# EvaluationV1_0.net
KiCad netlist of a schematic drawn in Altium Designer
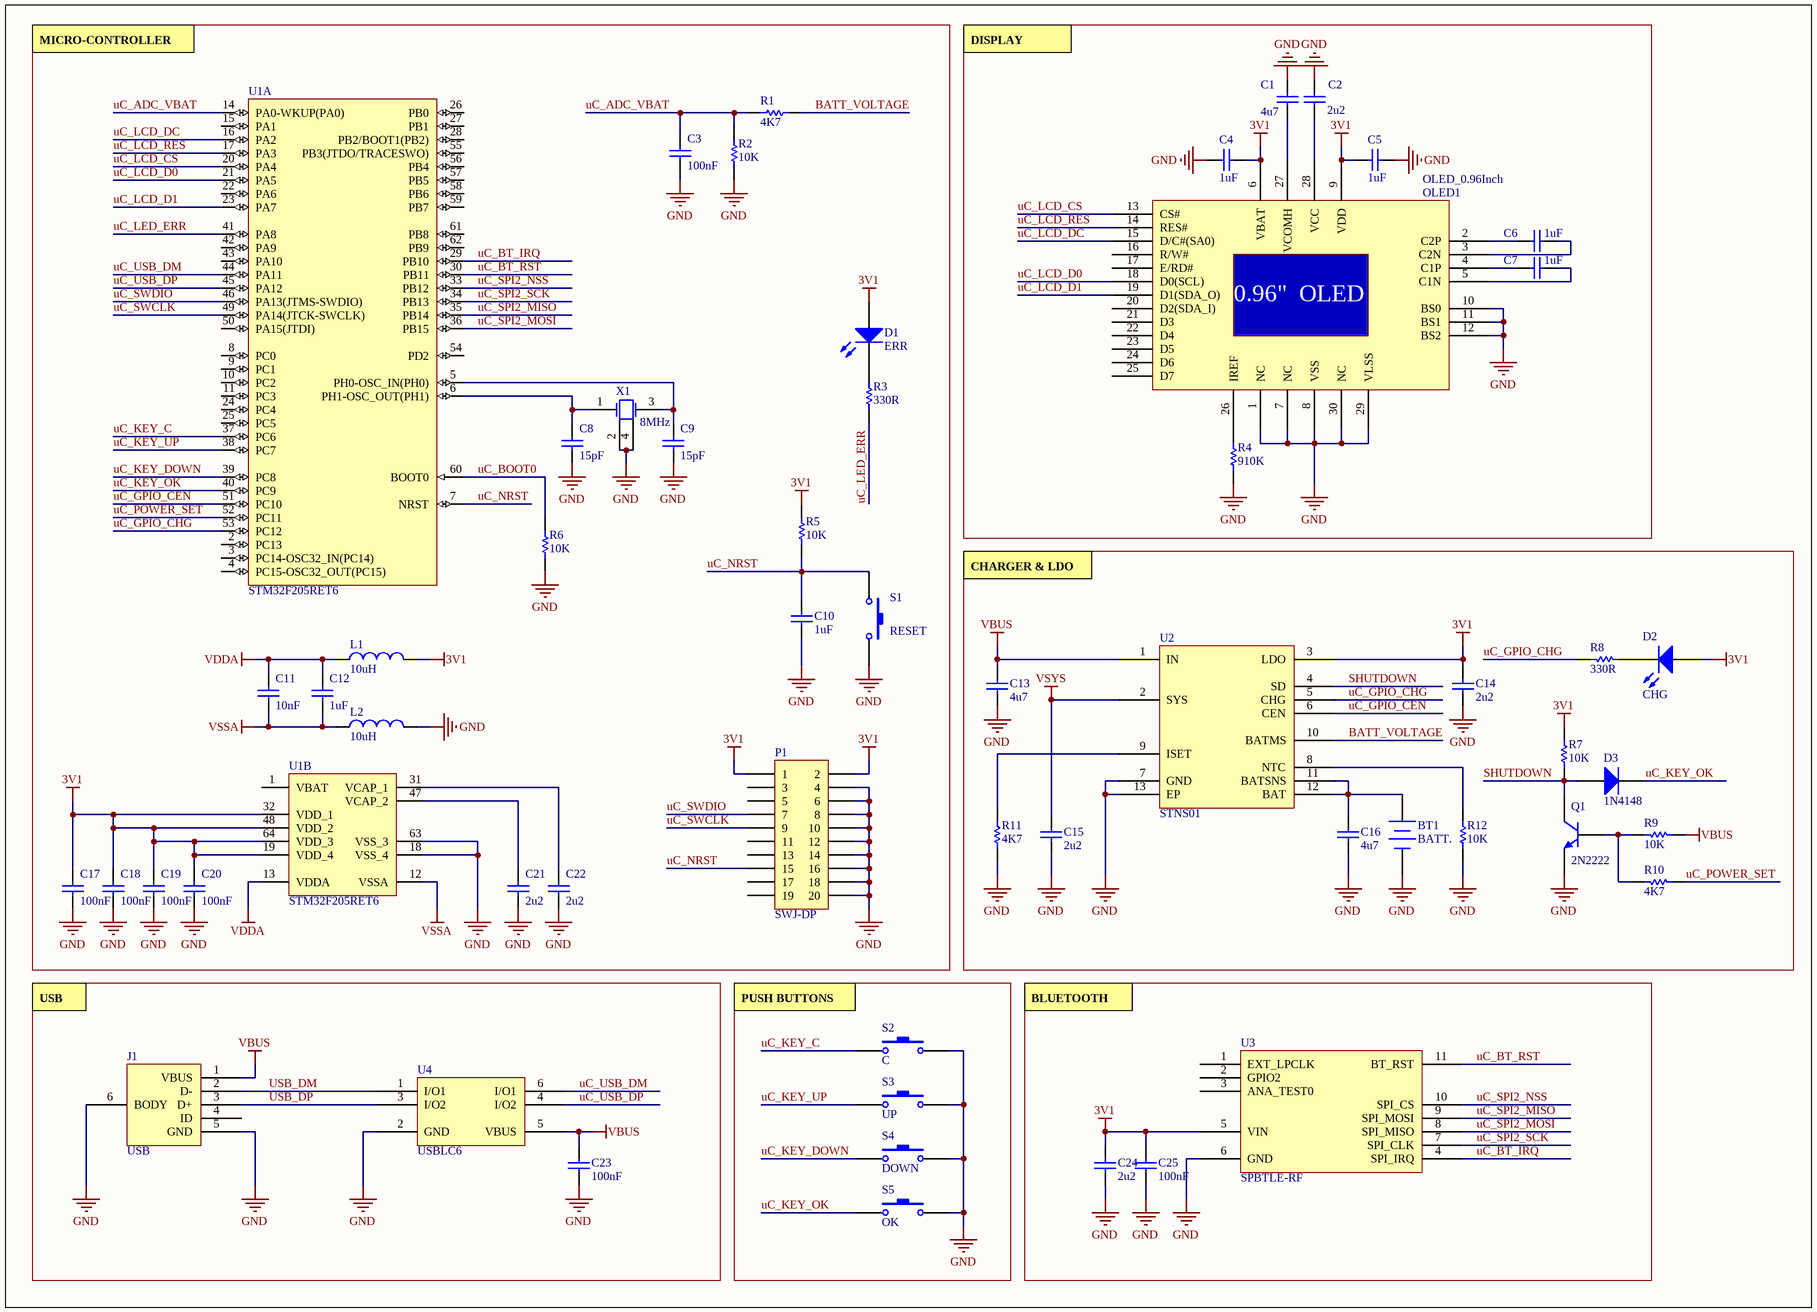
[diagram p0: EvaluationV1.0.SchDoc]

(export (version "E")
  (design (tool "Eeschema 10.0.6"))
  (components
    (comp (ref "BT1")
      (value "BATT.")
      (footprint "PH B2B")
      (description "Multicell Battery")
      (fields (field (name "PUBLISHER") "Altium Limited"))
      (libsource (lib "Miscellaneous Devices") (part "Battery"))
    )
    (comp (ref "C1")
      (value "4u7")
      (footprint "CAP 0805")
      (description "Multi Layer Capacitor")
      (libsource (lib "poyaLibrary") (part "CAP"))
    )
    (comp (ref "C2")
      (value "2u2")
      (footprint "CAP 0805")
      (description "Multi Layer Capacitor")
      (libsource (lib "poyaLibrary") (part "CAP"))
    )
    (comp (ref "C3")
      (value "100nF")
      (footprint "CAP 0805")
      (description "Multi Layer Capacitor")
      (libsource (lib "poyaLibrary") (part "CAP"))
    )
    (comp (ref "C4")
      (value "1uF")
      (footprint "CAP 0805")
      (description "Multi Layer Capacitor")
      (libsource (lib "poyaLibrary") (part "CAP"))
    )
    (comp (ref "C5")
      (value "1uF")
      (footprint "CAP 0805")
      (description "Multi Layer Capacitor")
      (libsource (lib "poyaLibrary") (part "CAP"))
    )
    (comp (ref "C6")
      (value "1uF")
      (footprint "CAP 0805")
      (description "Multi Layer Capacitor")
      (libsource (lib "poyaLibrary") (part "CAP"))
    )
    (comp (ref "C7")
      (value "1uF")
      (footprint "CAP 0805")
      (description "Multi Layer Capacitor")
      (libsource (lib "poyaLibrary") (part "CAP"))
    )
    (comp (ref "C8")
      (value "15pF")
      (footprint "CAP 0805")
      (description "Multi Layer Capacitor")
      (libsource (lib "poyaLibrary") (part "CAP"))
    )
    (comp (ref "C9")
      (value "15pF")
      (footprint "CAP 0805")
      (description "Multi Layer Capacitor")
      (libsource (lib "poyaLibrary") (part "CAP"))
    )
    (comp (ref "C10")
      (value "1uF")
      (footprint "CAP 0805")
      (description "Multi Layer Capacitor")
      (libsource (lib "poyaLibrary") (part "CAP"))
    )
    (comp (ref "C11")
      (value "10nF")
      (footprint "CAP 0805")
      (description "Multi Layer Capacitor")
      (libsource (lib "poyaLibrary") (part "CAP"))
    )
    (comp (ref "C12")
      (value "1uF")
      (footprint "CAP 0805")
      (description "Multi Layer Capacitor")
      (libsource (lib "poyaLibrary") (part "CAP"))
    )
    (comp (ref "C13")
      (value "4u7")
      (footprint "CAP 0805")
      (description "Multi Layer Capacitor")
      (libsource (lib "poyaLibrary") (part "CAP"))
    )
    (comp (ref "C14")
      (value "2u2")
      (footprint "CAP 0805")
      (description "Multi Layer Capacitor")
      (libsource (lib "poyaLibrary") (part "CAP"))
    )
    (comp (ref "C15")
      (value "2u2")
      (footprint "CAP 0805")
      (description "Multi Layer Capacitor")
      (libsource (lib "poyaLibrary") (part "CAP"))
    )
    (comp (ref "C16")
      (value "4u7")
      (footprint "CAP 0805")
      (description "Multi Layer Capacitor")
      (libsource (lib "poyaLibrary") (part "CAP"))
    )
    (comp (ref "C17")
      (value "100nF")
      (footprint "CAP 0805")
      (description "Multi Layer Capacitor")
      (libsource (lib "poyaLibrary") (part "CAP"))
    )
    (comp (ref "C18")
      (value "100nF")
      (footprint "CAP 0805")
      (description "Multi Layer Capacitor")
      (libsource (lib "poyaLibrary") (part "CAP"))
    )
    (comp (ref "C19")
      (value "100nF")
      (footprint "CAP 0805")
      (description "Multi Layer Capacitor")
      (libsource (lib "poyaLibrary") (part "CAP"))
    )
    (comp (ref "C20")
      (value "100nF")
      (footprint "CAP 0805")
      (description "Multi Layer Capacitor")
      (libsource (lib "poyaLibrary") (part "CAP"))
    )
    (comp (ref "C21")
      (value "2u2")
      (footprint "CAP 0805")
      (description "Multi Layer Capacitor")
      (libsource (lib "poyaLibrary") (part "CAP"))
    )
    (comp (ref "C22")
      (value "2u2")
      (footprint "CAP 0805")
      (description "Multi Layer Capacitor")
      (libsource (lib "poyaLibrary") (part "CAP"))
    )
    (comp (ref "C23")
      (value "100nF")
      (footprint "CAP 0805")
      (description "Multi Layer Capacitor")
      (libsource (lib "poyaLibrary") (part "CAP"))
    )
    (comp (ref "C24")
      (value "2u2")
      (footprint "CAP 0805")
      (description "Multi Layer Capacitor")
      (libsource (lib "poyaLibrary") (part "CAP"))
    )
    (comp (ref "C25")
      (value "100nF")
      (footprint "CAP 0805")
      (description "Multi Layer Capacitor")
      (libsource (lib "poyaLibrary") (part "CAP"))
    )
    (comp (ref "D1")
      (value "ERR")
      (footprint "LED 0805")
      (description "Typical RED, GREEN, YELLOW, AMBER GaAs LED")
      (fields (field (name "PUBLISHER") "Altium Limited"))
      (libsource (lib "Miscellaneous Devices") (part "LED2"))
    )
    (comp (ref "D2")
      (value "CHG")
      (footprint "LED 0805")
      (description "Typical RED, GREEN, YELLOW, AMBER GaAs LED")
      (fields (field (name "PUBLISHER") "Altium Limited"))
      (libsource (lib "Miscellaneous Devices") (part "LED2"))
    )
    (comp (ref "D3")
      (value "1N4148")
      (footprint "DIODE SOD-80")
      (description "Diode")
      (libsource (lib "poyaLibrary") (part "DIODE"))
    )
    (comp (ref "J1")
      (value "USB")
      (footprint "USB_MICRO")
      (description "Micro USB Connector")
      (libsource (lib "poyaLibrary") (part "USB MICRO"))
    )
    (comp (ref "L1")
      (value "10uH")
      (footprint "RES 0805")
      (description "INDUCTOR")
      (libsource (lib "poyaLibrary") (part "INDUCTOR"))
    )
    (comp (ref "L2")
      (value "10uH")
      (footprint "RES 0805")
      (description "INDUCTOR")
      (libsource (lib "poyaLibrary") (part "INDUCTOR"))
    )
    (comp (ref "OLED1")
      (value "OLED_0.96Inch")
      (footprint "OLED 0.96\"")
      (libsource (lib "HW") (part "OLED_0.96"))
    )
    (comp (ref "P1")
      (value "SWJ-DP")
      (footprint "BOX 2X10")
      (description "Header, 10-Pin, Dual row")
      (fields (field (name "PUBLISHER") "Altium Limited"))
      (libsource (lib "Miscellaneous Connectors") (part "Header 10X2"))
    )
    (comp (ref "Q1")
      (value "2N2222")
      (footprint "SOT23")
      (description "NPN Transistor")
      (libsource (lib "poyaLibrary") (part "NPN"))
    )
    (comp (ref "R1")
      (value "4K7")
      (footprint "RES 0805")
      (description "Resistor")
      (libsource (lib "poyaLibrary") (part "RES"))
    )
    (comp (ref "R2")
      (value "10K")
      (footprint "RES 0805")
      (description "Resistor")
      (libsource (lib "poyaLibrary") (part "RES"))
    )
    (comp (ref "R3")
      (value "330R")
      (footprint "RES 0805")
      (description "Resistor")
      (libsource (lib "poyaLibrary") (part "RES"))
    )
    (comp (ref "R4")
      (value "910K")
      (footprint "RES 0805")
      (description "Resistor")
      (libsource (lib "poyaLibrary") (part "RES"))
    )
    (comp (ref "R5")
      (value "10K")
      (footprint "RES 0805")
      (description "Resistor")
      (libsource (lib "poyaLibrary") (part "RES"))
    )
    (comp (ref "R6")
      (value "10K")
      (footprint "RES 0805")
      (description "Resistor")
      (libsource (lib "poyaLibrary") (part "RES"))
    )
    (comp (ref "R7")
      (value "10K")
      (footprint "RES 0805")
      (description "Resistor")
      (libsource (lib "poyaLibrary") (part "RES"))
    )
    (comp (ref "R8")
      (value "330R")
      (footprint "RES 0805")
      (description "Resistor")
      (libsource (lib "poyaLibrary") (part "RES"))
    )
    (comp (ref "R9")
      (value "10K")
      (footprint "RES 0805")
      (description "Resistor")
      (libsource (lib "poyaLibrary") (part "RES"))
    )
    (comp (ref "R10")
      (value "4K7")
      (footprint "RES 0805")
      (description "Resistor")
      (libsource (lib "poyaLibrary") (part "RES"))
    )
    (comp (ref "R11")
      (value "4K7")
      (footprint "RES 0805")
      (description "Resistor")
      (libsource (lib "poyaLibrary") (part "RES"))
    )
    (comp (ref "R12")
      (value "10K")
      (footprint "RES 0805")
      (description "Resistor")
      (libsource (lib "poyaLibrary") (part "RES"))
    )
    (comp (ref "S1")
      (value "RESET")
      (footprint "SW SMD 6x6x5")
      (description "Switch")
      (fields (field (name "PUBLISHER") "Altium Limited"))
      (libsource (lib "Miscellaneous Devices") (part "SW-PB"))
    )
    (comp (ref "S2")
      (value "C")
      (footprint "SW SMD 6x6x5")
      (description "Switch")
      (fields (field (name "PUBLISHER") "Altium Limited"))
      (libsource (lib "Miscellaneous Devices") (part "SW-PB"))
    )
    (comp (ref "S3")
      (value "UP")
      (footprint "SW SMD 6x6x5")
      (description "Switch")
      (fields (field (name "PUBLISHER") "Altium Limited"))
      (libsource (lib "Miscellaneous Devices") (part "SW-PB"))
    )
    (comp (ref "S4")
      (value "DOWN")
      (footprint "SW SMD 6x6x5")
      (description "Switch")
      (fields (field (name "PUBLISHER") "Altium Limited"))
      (libsource (lib "Miscellaneous Devices") (part "SW-PB"))
    )
    (comp (ref "S5")
      (value "OK")
      (footprint "SW SMD 6x6x5")
      (description "Switch")
      (fields (field (name "PUBLISHER") "Altium Limited"))
      (libsource (lib "Miscellaneous Devices") (part "SW-PB"))
    )
    (comp (ref "U1")
      (value "STM32F205RET6")
      (footprint "LQFP64_N")
      (libsource (lib "STMicroelectronics STM32 F2") (part "STM32F205RET6"))
    )
    (comp (ref "U2")
      (value "STNS01")
      (footprint "DFN12-3x3")
      (description "Li-Ion linear battery charger with LDO")
      (libsource (lib "poyaLibrary") (part "STNS01"))
    )
    (comp (ref "U3")
      (value "SPBTLE-RF")
      (footprint "SPBTLE-RF")
      (description "Very low power network processor module for Bluetooth® low\r\nenergy v4.1")
      (libsource (lib "poyaLibrary") (part "SPBTLE-RF"))
    )
    (comp (ref "U4")
      (value "USBLC6")
      (footprint "SOT-666")
      (description "ESD Protection for USB 2.0")
      (libsource (lib "poyaLibrary") (part "USBLC6"))
    )
    (comp (ref "X1") (value "8MHz") (footprint "ABMM2") (libsource (lib "poyaLibrary") (part "XTAL2")))
  )
  (nets
    (net (code "1") (name "/BATT_VOLTAGE") (class "Default")
      (node (ref "R1") (pin "1") (pinfunction "1_1") (pintype "passive"))
      (node (ref "U2") (pin "10") (pinfunction "BATMS_10") (pintype "passive"))
    )
    (net (code "2") (name "/SHUTDOWN") (class "Default")
      (node (ref "D3") (pin "1") (pinfunction "A_1") (pintype "passive"))
      (node (ref "Q1") (pin "2") (pinfunction "C_2") (pintype "passive"))
      (node (ref "R7") (pin "2") (pinfunction "2_2") (pintype "passive"))
      (node (ref "U2") (pin "4") (pinfunction "SD_4") (pintype "passive"))
    )
    (net (code "3") (name "/USB_DM") (class "Default")
      (node (ref "J1") (pin "2") (pinfunction "D-_2") (pintype "passive"))
      (node (ref "U4") (pin "1") (pinfunction "I/O1_1") (pintype "passive"))
    )
    (net (code "4") (name "/USB_DP") (class "Default")
      (node (ref "J1") (pin "3") (pinfunction "D+_3") (pintype "passive"))
      (node (ref "U4") (pin "3") (pinfunction "I/O2_3") (pintype "passive"))
    )
    (net (code "5") (name "/uC_ADC_VBAT") (class "Default")
      (node (ref "C3") (pin "2") (pinfunction "2_2") (pintype "passive"))
      (node (ref "R1") (pin "2") (pinfunction "2_2") (pintype "passive"))
      (node (ref "R2") (pin "1") (pinfunction "1_1") (pintype "passive"))
      (node (ref "U1") (pin "14") (pinfunction "PA0-WKUP(PA0)_14") (pintype "bidirectional"))
    )
    (net (code "6") (name "/uC_BOOT0") (class "Default")
      (node (ref "R6") (pin "2") (pinfunction "2_2") (pintype "passive"))
      (node (ref "U1") (pin "60") (pinfunction "BOOT0_60") (pintype "input"))
    )
    (net (code "7") (name "/uC_BT_IRQ") (class "Default")
      (node (ref "U1") (pin "29") (pinfunction "PB10_29") (pintype "bidirectional"))
      (node (ref "U3") (pin "4") (pinfunction "SPI_IRQ_4") (pintype "passive"))
    )
    (net (code "8") (name "/uC_BT_RST") (class "Default")
      (node (ref "U1") (pin "30") (pinfunction "PB11_30") (pintype "bidirectional"))
      (node (ref "U3") (pin "11") (pinfunction "BT_RST_11") (pintype "passive"))
    )
    (net (code "9") (name "/uC_GPIO_CEN") (class "Default")
      (node (ref "U1") (pin "51") (pinfunction "PC10_51") (pintype "bidirectional"))
      (node (ref "U2") (pin "6") (pinfunction "CEN_6") (pintype "passive"))
    )
    (net (code "10") (name "/uC_GPIO_CHG") (class "Default")
      (node (ref "R8") (pin "1") (pinfunction "1_1") (pintype "passive"))
      (node (ref "U1") (pin "53") (pinfunction "PC12_53") (pintype "bidirectional"))
      (node (ref "U2") (pin "5") (pinfunction "CHG_5") (pintype "passive"))
    )
    (net (code "11") (name "/uC_KEY_C") (class "Default")
      (node (ref "S2") (pin "1") (pinfunction "1_1") (pintype "passive"))
      (node (ref "U1") (pin "37") (pinfunction "PC6_37") (pintype "bidirectional"))
    )
    (net (code "12") (name "/uC_KEY_DOWN") (class "Default")
      (node (ref "S4") (pin "1") (pinfunction "1_1") (pintype "passive"))
      (node (ref "U1") (pin "39") (pinfunction "PC8_39") (pintype "bidirectional"))
    )
    (net (code "13") (name "/uC_KEY_OK") (class "Default")
      (node (ref "D3") (pin "2") (pinfunction "K_2") (pintype "passive"))
      (node (ref "S5") (pin "1") (pinfunction "1_1") (pintype "passive"))
      (node (ref "U1") (pin "40") (pinfunction "PC9_40") (pintype "bidirectional"))
    )
    (net (code "14") (name "/uC_KEY_UP") (class "Default")
      (node (ref "S3") (pin "1") (pinfunction "1_1") (pintype "passive"))
      (node (ref "U1") (pin "38") (pinfunction "PC7_38") (pintype "bidirectional"))
    )
    (net (code "15") (name "/uC_LCD_CS") (class "Default")
      (node (ref "OLED1") (pin "13") (pinfunction "CS#_13") (pintype "passive"))
      (node (ref "U1") (pin "20") (pinfunction "PA4_20") (pintype "bidirectional"))
    )
    (net (code "16") (name "/uC_LCD_D0") (class "Default")
      (node (ref "OLED1") (pin "18") (pinfunction "D0(SCL)_18") (pintype "passive"))
      (node (ref "U1") (pin "21") (pinfunction "PA5_21") (pintype "bidirectional"))
    )
    (net (code "17") (name "/uC_LCD_D1") (class "Default")
      (node (ref "OLED1") (pin "19") (pinfunction "D1(SDA_O)_19") (pintype "passive"))
      (node (ref "U1") (pin "23") (pinfunction "PA7_23") (pintype "bidirectional"))
    )
    (net (code "18") (name "/uC_LCD_DC") (class "Default")
      (node (ref "OLED1") (pin "15") (pinfunction "D/C#(SA0)_15") (pintype "passive"))
      (node (ref "U1") (pin "16") (pinfunction "PA2_16") (pintype "bidirectional"))
    )
    (net (code "19") (name "/uC_LCD_RES") (class "Default")
      (node (ref "OLED1") (pin "14") (pinfunction "RES#_14") (pintype "passive"))
      (node (ref "U1") (pin "17") (pinfunction "PA3_17") (pintype "bidirectional"))
    )
    (net (code "20") (name "/uC_LED_ERR") (class "Default")
      (node (ref "R3") (pin "2") (pinfunction "2_2") (pintype "passive"))
      (node (ref "U1") (pin "41") (pinfunction "PA8_41") (pintype "bidirectional"))
    )
    (net (code "21") (name "/uC_NRST") (class "Default")
      (node (ref "C10") (pin "1") (pinfunction "1_1") (pintype "passive"))
      (node (ref "P1") (pin "15") (pinfunction "15_15") (pintype "passive"))
      (node (ref "R5") (pin "1") (pinfunction "1_1") (pintype "passive"))
      (node (ref "S1") (pin "1") (pinfunction "1_1") (pintype "passive"))
      (node (ref "U1") (pin "7") (pinfunction "NRST_7") (pintype "bidirectional"))
    )
    (net (code "22") (name "/uC_POWER_SET") (class "Default")
      (node (ref "R10") (pin "1") (pinfunction "1_1") (pintype "passive"))
      (node (ref "U1") (pin "52") (pinfunction "PC11_52") (pintype "bidirectional"))
    )
    (net (code "23") (name "/uC_SPI2_MISO") (class "Default")
      (node (ref "U1") (pin "35") (pinfunction "PB14_35") (pintype "bidirectional"))
      (node (ref "U3") (pin "9") (pinfunction "SPI_MOSI_9") (pintype "passive"))
    )
    (net (code "24") (name "/uC_SPI2_MOSI") (class "Default")
      (node (ref "U1") (pin "36") (pinfunction "PB15_36") (pintype "bidirectional"))
      (node (ref "U3") (pin "8") (pinfunction "SPI_MISO_8") (pintype "passive"))
    )
    (net (code "25") (name "/uC_SPI2_NSS") (class "Default")
      (node (ref "U1") (pin "33") (pinfunction "PB12_33") (pintype "bidirectional"))
      (node (ref "U3") (pin "10") (pinfunction "SPI_CS_10") (pintype "passive"))
    )
    (net (code "26") (name "/uC_SPI2_SCK") (class "Default")
      (node (ref "U1") (pin "34") (pinfunction "PB13_34") (pintype "bidirectional"))
      (node (ref "U3") (pin "7") (pinfunction "SPI_CLK_7") (pintype "passive"))
    )
    (net (code "27") (name "/uC_SWCLK") (class "Default")
      (node (ref "P1") (pin "9") (pinfunction "9_9") (pintype "passive"))
      (node (ref "U1") (pin "49") (pinfunction "PA14(JTCK-SWCLK)_49") (pintype "bidirectional"))
    )
    (net (code "28") (name "/uC_SWDIO") (class "Default")
      (node (ref "P1") (pin "7") (pinfunction "7_7") (pintype "passive"))
      (node (ref "U1") (pin "46") (pinfunction "PA13(JTMS-SWDIO)_46") (pintype "bidirectional"))
    )
    (net (code "29") (name "/uC_USB_DM") (class "Default")
      (node (ref "U1") (pin "44") (pinfunction "PA11_44") (pintype "bidirectional"))
      (node (ref "U4") (pin "6") (pinfunction "I/O1_6") (pintype "passive"))
    )
    (net (code "30") (name "/uC_USB_DP") (class "Default")
      (node (ref "U1") (pin "45") (pinfunction "PA12_45") (pintype "bidirectional"))
      (node (ref "U4") (pin "4") (pinfunction "I/O2_4") (pintype "passive"))
    )
    (net (code "31") (name "3V1") (class "Default")
      (node (ref "C14") (pin "1") (pinfunction "1_1") (pintype "passive"))
      (node (ref "C17") (pin "2") (pinfunction "2_2") (pintype "passive"))
      (node (ref "C18") (pin "2") (pinfunction "2_2") (pintype "passive"))
      (node (ref "C19") (pin "2") (pinfunction "2_2") (pintype "passive"))
      (node (ref "C20") (pin "2") (pinfunction "2_2") (pintype "passive"))
      (node (ref "C24") (pin "1") (pinfunction "1_1") (pintype "passive"))
      (node (ref "C25") (pin "1") (pinfunction "1_1") (pintype "passive"))
      (node (ref "C4") (pin "2") (pinfunction "2_2") (pintype "passive"))
      (node (ref "C5") (pin "2") (pinfunction "2_2") (pintype "passive"))
      (node (ref "D1") (pin "1") (pinfunction "A_1") (pintype "passive"))
      (node (ref "D2") (pin "1") (pinfunction "A_1") (pintype "passive"))
      (node (ref "L1") (pin "1") (pinfunction "1_1") (pintype "passive"))
      (node (ref "OLED1") (pin "6") (pinfunction "VBAT_6") (pintype "passive"))
      (node (ref "OLED1") (pin "9") (pinfunction "VDD_9") (pintype "passive"))
      (node (ref "P1") (pin "1") (pinfunction "1_1") (pintype "passive"))
      (node (ref "P1") (pin "2") (pinfunction "2_2") (pintype "passive"))
      (node (ref "R5") (pin "2") (pinfunction "2_2") (pintype "passive"))
      (node (ref "R7") (pin "1") (pinfunction "1_1") (pintype "passive"))
      (node (ref "U1") (pin "19") (pinfunction "VDD_4_19") (pintype "power_in"))
      (node (ref "U1") (pin "32") (pinfunction "VDD_1_32") (pintype "power_in"))
      (node (ref "U1") (pin "48") (pinfunction "VDD_2_48") (pintype "power_in"))
      (node (ref "U1") (pin "64") (pinfunction "VDD_3_64") (pintype "power_in"))
      (node (ref "U2") (pin "3") (pinfunction "LDO_3") (pintype "passive"))
      (node (ref "U3") (pin "5") (pinfunction "VIN_5") (pintype "passive"))
    )
    (net (code "32") (name "GND") (class "Default")
      (node (ref "BT1") (pin "2") (pinfunction "-_2") (pintype "passive"))
      (node (ref "C1") (pin "1") (pinfunction "1_1") (pintype "passive"))
      (node (ref "C10") (pin "2") (pinfunction "2_2") (pintype "passive"))
      (node (ref "C13") (pin "2") (pinfunction "2_2") (pintype "passive"))
      (node (ref "C14") (pin "2") (pinfunction "2_2") (pintype "passive"))
      (node (ref "C15") (pin "2") (pinfunction "2_2") (pintype "passive"))
      (node (ref "C16") (pin "2") (pinfunction "2_2") (pintype "passive"))
      (node (ref "C17") (pin "1") (pinfunction "1_1") (pintype "passive"))
      (node (ref "C18") (pin "1") (pinfunction "1_1") (pintype "passive"))
      (node (ref "C19") (pin "1") (pinfunction "1_1") (pintype "passive"))
      (node (ref "C2") (pin "1") (pinfunction "1_1") (pintype "passive"))
      (node (ref "C20") (pin "1") (pinfunction "1_1") (pintype "passive"))
      (node (ref "C21") (pin "1") (pinfunction "1_1") (pintype "passive"))
      (node (ref "C22") (pin "1") (pinfunction "1_1") (pintype "passive"))
      (node (ref "C23") (pin "1") (pinfunction "1_1") (pintype "passive"))
      (node (ref "C24") (pin "2") (pinfunction "2_2") (pintype "passive"))
      (node (ref "C25") (pin "2") (pinfunction "2_2") (pintype "passive"))
      (node (ref "C3") (pin "1") (pinfunction "1_1") (pintype "passive"))
      (node (ref "C4") (pin "1") (pinfunction "1_1") (pintype "passive"))
      (node (ref "C5") (pin "1") (pinfunction "1_1") (pintype "passive"))
      (node (ref "C8") (pin "1") (pinfunction "1_1") (pintype "passive"))
      (node (ref "C9") (pin "1") (pinfunction "1_1") (pintype "passive"))
      (node (ref "J1") (pin "5") (pinfunction "GND_5") (pintype "passive"))
      (node (ref "J1") (pin "6") (pinfunction "BODY_6") (pintype "passive"))
      (node (ref "L2") (pin "1") (pinfunction "1_1") (pintype "passive"))
      (node (ref "OLED1") (pin "1") (pinfunction "NC_1") (pintype "passive"))
      (node (ref "OLED1") (pin "10") (pinfunction "BS0_10") (pintype "passive"))
      (node (ref "OLED1") (pin "11") (pinfunction "BS1_11") (pintype "passive"))
      (node (ref "OLED1") (pin "12") (pinfunction "BS2_12") (pintype "passive"))
      (node (ref "OLED1") (pin "29") (pinfunction "VLSS_29") (pintype "passive"))
      (node (ref "OLED1") (pin "30") (pinfunction "NC_30") (pintype "passive"))
      (node (ref "OLED1") (pin "7") (pinfunction "NC_7") (pintype "passive"))
      (node (ref "OLED1") (pin "8") (pinfunction "VSS_8") (pintype "passive"))
      (node (ref "P1") (pin "10") (pinfunction "10_10") (pintype "passive"))
      (node (ref "P1") (pin "12") (pinfunction "12_12") (pintype "passive"))
      (node (ref "P1") (pin "14") (pinfunction "14_14") (pintype "passive"))
      (node (ref "P1") (pin "16") (pinfunction "16_16") (pintype "passive"))
      (node (ref "P1") (pin "18") (pinfunction "18_18") (pintype "passive"))
      (node (ref "P1") (pin "20") (pinfunction "20_20") (pintype "passive"))
      (node (ref "P1") (pin "4") (pinfunction "4_4") (pintype "passive"))
      (node (ref "P1") (pin "6") (pinfunction "6_6") (pintype "passive"))
      (node (ref "P1") (pin "8") (pinfunction "8_8") (pintype "passive"))
      (node (ref "Q1") (pin "3") (pinfunction "E_3") (pintype "passive"))
      (node (ref "R11") (pin "1") (pinfunction "1_1") (pintype "passive"))
      (node (ref "R12") (pin "1") (pinfunction "1_1") (pintype "passive"))
      (node (ref "R2") (pin "2") (pinfunction "2_2") (pintype "passive"))
      (node (ref "R4") (pin "1") (pinfunction "1_1") (pintype "passive"))
      (node (ref "R6") (pin "1") (pinfunction "1_1") (pintype "passive"))
      (node (ref "S1") (pin "2") (pinfunction "2_2") (pintype "passive"))
      (node (ref "S2") (pin "2") (pinfunction "2_2") (pintype "passive"))
      (node (ref "S3") (pin "2") (pinfunction "2_2") (pintype "passive"))
      (node (ref "S4") (pin "2") (pinfunction "2_2") (pintype "passive"))
      (node (ref "S5") (pin "2") (pinfunction "2_2") (pintype "passive"))
      (node (ref "U1") (pin "18") (pinfunction "VSS_4_18") (pintype "power_in"))
      (node (ref "U1") (pin "63") (pinfunction "VSS_3_63") (pintype "power_in"))
      (node (ref "U2") (pin "13") (pinfunction "EP_13") (pintype "passive"))
      (node (ref "U2") (pin "7") (pinfunction "GND_7") (pintype "passive"))
      (node (ref "U3") (pin "6") (pinfunction "GND_6") (pintype "passive"))
      (node (ref "U4") (pin "2") (pinfunction "GND_2") (pintype "passive"))
      (node (ref "X1") (pin "2") (pinfunction "2_2") (pintype "passive"))
      (node (ref "X1") (pin "4") (pinfunction "4_4") (pintype "passive"))
    )
    (net (code "33") (name "Net-(BT1-+)") (class "Default")
      (node (ref "BT1") (pin "1") (pinfunction "+_1") (pintype "passive"))
      (node (ref "C16") (pin "1") (pinfunction "1_1") (pintype "passive"))
      (node (ref "U2") (pin "11") (pinfunction "BATSNS_11") (pintype "passive"))
      (node (ref "U2") (pin "12") (pinfunction "BAT_12") (pintype "passive"))
    )
    (net (code "34") (name "Net-(D1-K)") (class "Default")
      (node (ref "D1") (pin "2") (pinfunction "K_2") (pintype "passive"))
      (node (ref "R3") (pin "1") (pinfunction "1_1") (pintype "passive"))
    )
    (net (code "35") (name "Net-(D2-K)") (class "Default")
      (node (ref "D2") (pin "2") (pinfunction "K_2") (pintype "passive"))
      (node (ref "R8") (pin "2") (pinfunction "2_2") (pintype "passive"))
    )
    (net (code "36") (name "Net-(OLED1-C1N)") (class "Default")
      (node (ref "C7") (pin "1") (pinfunction "1_1") (pintype "passive"))
      (node (ref "OLED1") (pin "5") (pinfunction "C1N_5") (pintype "passive"))
    )
    (net (code "37") (name "Net-(OLED1-C1P)") (class "Default")
      (node (ref "C7") (pin "2") (pinfunction "2_2") (pintype "passive"))
      (node (ref "OLED1") (pin "4") (pinfunction "C1P_4") (pintype "passive"))
    )
    (net (code "38") (name "Net-(OLED1-C2N)") (class "Default")
      (node (ref "C6") (pin "1") (pinfunction "1_1") (pintype "passive"))
      (node (ref "OLED1") (pin "3") (pinfunction "C2N_3") (pintype "passive"))
    )
    (net (code "39") (name "Net-(OLED1-C2P)") (class "Default")
      (node (ref "C6") (pin "2") (pinfunction "2_2") (pintype "passive"))
      (node (ref "OLED1") (pin "2") (pinfunction "C2P_2") (pintype "passive"))
    )
    (net (code "40") (name "Net-(OLED1-IREF)") (class "Default")
      (node (ref "OLED1") (pin "26") (pinfunction "IREF_26") (pintype "passive"))
      (node (ref "R4") (pin "2") (pinfunction "2_2") (pintype "passive"))
    )
    (net (code "41") (name "Net-(OLED1-VCC)") (class "Default")
      (node (ref "C2") (pin "2") (pinfunction "2_2") (pintype "passive"))
      (node (ref "OLED1") (pin "28") (pinfunction "VCC_28") (pintype "passive"))
    )
    (net (code "42") (name "Net-(OLED1-VCOMH)") (class "Default")
      (node (ref "C1") (pin "2") (pinfunction "2_2") (pintype "passive"))
      (node (ref "OLED1") (pin "27") (pinfunction "VCOMH_27") (pintype "passive"))
    )
    (net (code "43") (name "Net-(Q1-B)") (class "Default")
      (node (ref "Q1") (pin "1") (pinfunction "B_1") (pintype "passive"))
      (node (ref "R10") (pin "2") (pinfunction "2_2") (pintype "passive"))
      (node (ref "R9") (pin "2") (pinfunction "2_2") (pintype "passive"))
    )
    (net (code "44") (name "Net-(U1A-PH0-OSC_IN(PH0))") (class "Default")
      (node (ref "C9") (pin "2") (pinfunction "2_2") (pintype "passive"))
      (node (ref "U1") (pin "5") (pinfunction "PH0-OSC_IN(PH0)_5") (pintype "bidirectional"))
      (node (ref "X1") (pin "3") (pinfunction "3_3") (pintype "passive"))
    )
    (net (code "45") (name "Net-(U1A-PH1-OSC_OUT(PH1))") (class "Default")
      (node (ref "C8") (pin "2") (pinfunction "2_2") (pintype "passive"))
      (node (ref "U1") (pin "6") (pinfunction "PH1-OSC_OUT(PH1)_6") (pintype "bidirectional"))
      (node (ref "X1") (pin "1") (pinfunction "1_1") (pintype "passive"))
    )
    (net (code "46") (name "Net-(U1B-VCAP_1)") (class "Default")
      (node (ref "C22") (pin "2") (pinfunction "2_2") (pintype "passive"))
      (node (ref "U1") (pin "31") (pinfunction "VCAP_1_31") (pintype "power_in"))
    )
    (net (code "47") (name "Net-(U1B-VCAP_2)") (class "Default")
      (node (ref "C21") (pin "2") (pinfunction "2_2") (pintype "passive"))
      (node (ref "U1") (pin "47") (pinfunction "VCAP_2_47") (pintype "power_in"))
    )
    (net (code "48") (name "Net-(U2-ISET)") (class "Default")
      (node (ref "R11") (pin "2") (pinfunction "2_2") (pintype "passive"))
      (node (ref "U2") (pin "9") (pinfunction "ISET_9") (pintype "passive"))
    )
    (net (code "49") (name "Net-(U2-NTC)") (class "Default")
      (node (ref "R12") (pin "2") (pinfunction "2_2") (pintype "passive"))
      (node (ref "U2") (pin "8") (pinfunction "NTC_8") (pintype "passive"))
    )
    (net (code "50") (name "VBUS") (class "Default")
      (node (ref "C13") (pin "1") (pinfunction "1_1") (pintype "passive"))
      (node (ref "C23") (pin "2") (pinfunction "2_2") (pintype "passive"))
      (node (ref "J1") (pin "1") (pinfunction "VBUS_1") (pintype "passive"))
      (node (ref "R9") (pin "1") (pinfunction "1_1") (pintype "passive"))
      (node (ref "U2") (pin "1") (pinfunction "IN_1") (pintype "passive"))
      (node (ref "U4") (pin "5") (pinfunction "VBUS_5") (pintype "passive"))
    )
    (net (code "51") (name "VDDA") (class "Default")
      (node (ref "C11") (pin "2") (pinfunction "2_2") (pintype "passive"))
      (node (ref "C12") (pin "2") (pinfunction "2_2") (pintype "passive"))
      (node (ref "L1") (pin "2") (pinfunction "2_2") (pintype "passive"))
      (node (ref "U1") (pin "13") (pinfunction "VDDA_13") (pintype "power_in"))
    )
    (net (code "52") (name "VSSA") (class "Default")
      (node (ref "C11") (pin "1") (pinfunction "1_1") (pintype "passive"))
      (node (ref "C12") (pin "1") (pinfunction "1_1") (pintype "passive"))
      (node (ref "L2") (pin "2") (pinfunction "2_2") (pintype "passive"))
      (node (ref "U1") (pin "12") (pinfunction "VSSA_12") (pintype "power_in"))
    )
    (net (code "53") (name "VSYS") (class "Default")
      (node (ref "C15") (pin "1") (pinfunction "1_1") (pintype "passive"))
      (node (ref "U2") (pin "2") (pinfunction "SYS_2") (pintype "passive"))
    )
    (net (code "54") (name "unconnected-(J1-ID-Pad4)") (class "Default")
      (node (ref "J1") (pin "4") (pinfunction "ID_4") (pintype "passive"))
    )
    (net (code "55") (name "unconnected-(OLED1-D2(SDA_I)-Pad20)") (class "Default")
      (node (ref "OLED1") (pin "20") (pinfunction "D2(SDA_I)_20") (pintype "passive"))
    )
    (net (code "56") (name "unconnected-(OLED1-D3-Pad21)") (class "Default")
      (node (ref "OLED1") (pin "21") (pinfunction "D3_21") (pintype "passive"))
    )
    (net (code "57") (name "unconnected-(OLED1-D4-Pad22)") (class "Default")
      (node (ref "OLED1") (pin "22") (pinfunction "D4_22") (pintype "passive"))
    )
    (net (code "58") (name "unconnected-(OLED1-D5-Pad23)") (class "Default")
      (node (ref "OLED1") (pin "23") (pinfunction "D5_23") (pintype "passive"))
    )
    (net (code "59") (name "unconnected-(OLED1-D6-Pad24)") (class "Default")
      (node (ref "OLED1") (pin "24") (pinfunction "D6_24") (pintype "passive"))
    )
    (net (code "60") (name "unconnected-(OLED1-D7-Pad25)") (class "Default")
      (node (ref "OLED1") (pin "25") (pinfunction "D7_25") (pintype "passive"))
    )
    (net (code "61") (name "unconnected-(OLED1-E{slash}RD#-Pad17)") (class "Default")
      (node (ref "OLED1") (pin "17") (pinfunction "E/RD#_17") (pintype "passive"))
    )
    (net (code "62") (name "unconnected-(OLED1-R{slash}W#-Pad16)") (class "Default")
      (node (ref "OLED1") (pin "16") (pinfunction "R/W#_16") (pintype "passive"))
    )
    (net (code "63") (name "unconnected-(P1-Pad3)") (class "Default")
      (node (ref "P1") (pin "3") (pinfunction "3_3") (pintype "passive"))
    )
    (net (code "64") (name "unconnected-(P1-Pad5)") (class "Default")
      (node (ref "P1") (pin "5") (pinfunction "5_5") (pintype "passive"))
    )
    (net (code "65") (name "unconnected-(P1-Pad11)") (class "Default")
      (node (ref "P1") (pin "11") (pinfunction "11_11") (pintype "passive"))
    )
    (net (code "66") (name "unconnected-(P1-Pad13)") (class "Default")
      (node (ref "P1") (pin "13") (pinfunction "13_13") (pintype "passive"))
    )
    (net (code "67") (name "unconnected-(P1-Pad17)") (class "Default")
      (node (ref "P1") (pin "17") (pinfunction "17_17") (pintype "passive"))
    )
    (net (code "68") (name "unconnected-(P1-Pad19)") (class "Default")
      (node (ref "P1") (pin "19") (pinfunction "19_19") (pintype "passive"))
    )
    (net (code "69") (name "unconnected-(U1A-PA1-Pad15)") (class "Default")
      (node (ref "U1") (pin "15") (pinfunction "PA1_15") (pintype "bidirectional"))
    )
    (net (code "70") (name "unconnected-(U1A-PA6-Pad22)") (class "Default")
      (node (ref "U1") (pin "22") (pinfunction "PA6_22") (pintype "bidirectional"))
    )
    (net (code "71") (name "unconnected-(U1A-PA9-Pad42)") (class "Default")
      (node (ref "U1") (pin "42") (pinfunction "PA9_42") (pintype "bidirectional"))
    )
    (net (code "72") (name "unconnected-(U1A-PA10-Pad43)") (class "Default")
      (node (ref "U1") (pin "43") (pinfunction "PA10_43") (pintype "bidirectional"))
    )
    (net (code "73") (name "unconnected-(U1A-PA15(JTDI)-Pad50)") (class "Default")
      (node (ref "U1") (pin "50") (pinfunction "PA15(JTDI)_50") (pintype "bidirectional"))
    )
    (net (code "74") (name "unconnected-(U1A-PB0-Pad26)") (class "Default")
      (node (ref "U1") (pin "26") (pinfunction "PB0_26") (pintype "bidirectional"))
    )
    (net (code "75") (name "unconnected-(U1A-PB1-Pad27)") (class "Default")
      (node (ref "U1") (pin "27") (pinfunction "PB1_27") (pintype "bidirectional"))
    )
    (net (code "76") (name "unconnected-(U1A-PB2{slash}BOOT1(PB2)-Pad28)") (class "Default")
      (node (ref "U1") (pin "28") (pinfunction "PB2/BOOT1(PB2)_28") (pintype "bidirectional"))
    )
    (net (code "77") (name "unconnected-(U1A-PB3(JTDO{slash}TRACESWO)-Pad55)") (class "Default")
      (node (ref "U1") (pin "55") (pinfunction "PB3(JTDO/TRACESWO)_55") (pintype "bidirectional"))
    )
    (net (code "78") (name "unconnected-(U1A-PB4-Pad56)") (class "Default")
      (node (ref "U1") (pin "56") (pinfunction "PB4_56") (pintype "bidirectional"))
    )
    (net (code "79") (name "unconnected-(U1A-PB5-Pad57)") (class "Default")
      (node (ref "U1") (pin "57") (pinfunction "PB5_57") (pintype "bidirectional"))
    )
    (net (code "80") (name "unconnected-(U1A-PB6-Pad58)") (class "Default")
      (node (ref "U1") (pin "58") (pinfunction "PB6_58") (pintype "bidirectional"))
    )
    (net (code "81") (name "unconnected-(U1A-PB7-Pad59)") (class "Default")
      (node (ref "U1") (pin "59") (pinfunction "PB7_59") (pintype "bidirectional"))
    )
    (net (code "82") (name "unconnected-(U1A-PB8-Pad61)") (class "Default")
      (node (ref "U1") (pin "61") (pinfunction "PB8_61") (pintype "bidirectional"))
    )
    (net (code "83") (name "unconnected-(U1A-PB9-Pad62)") (class "Default")
      (node (ref "U1") (pin "62") (pinfunction "PB9_62") (pintype "bidirectional"))
    )
    (net (code "84") (name "unconnected-(U1A-PC0-Pad8)") (class "Default")
      (node (ref "U1") (pin "8") (pinfunction "PC0_8") (pintype "bidirectional"))
    )
    (net (code "85") (name "unconnected-(U1A-PC1-Pad9)") (class "Default")
      (node (ref "U1") (pin "9") (pinfunction "PC1_9") (pintype "bidirectional"))
    )
    (net (code "86") (name "unconnected-(U1A-PC2-Pad10)") (class "Default")
      (node (ref "U1") (pin "10") (pinfunction "PC2_10") (pintype "bidirectional"))
    )
    (net (code "87") (name "unconnected-(U1A-PC3-Pad11)") (class "Default")
      (node (ref "U1") (pin "11") (pinfunction "PC3_11") (pintype "bidirectional"))
    )
    (net (code "88") (name "unconnected-(U1A-PC4-Pad24)") (class "Default")
      (node (ref "U1") (pin "24") (pinfunction "PC4_24") (pintype "bidirectional"))
    )
    (net (code "89") (name "unconnected-(U1A-PC5-Pad25)") (class "Default")
      (node (ref "U1") (pin "25") (pinfunction "PC5_25") (pintype "bidirectional"))
    )
    (net (code "90") (name "unconnected-(U1A-PC13-Pad2)") (class "Default")
      (node (ref "U1") (pin "2") (pinfunction "PC13_2") (pintype "bidirectional"))
    )
    (net (code "91") (name "unconnected-(U1A-PC14-OSC32_IN(PC14)-Pad3)") (class "Default")
      (node (ref "U1") (pin "3") (pinfunction "PC14-OSC32_IN(PC14)_3") (pintype "bidirectional"))
    )
    (net (code "92") (name "unconnected-(U1A-PC15-OSC32_OUT(PC15)-Pad4)") (class "Default")
      (node (ref "U1") (pin "4") (pinfunction "PC15-OSC32_OUT(PC15)_4") (pintype "bidirectional"))
    )
    (net (code "93") (name "unconnected-(U1A-PD2-Pad54)") (class "Default")
      (node (ref "U1") (pin "54") (pinfunction "PD2_54") (pintype "bidirectional"))
    )
    (net (code "94") (name "unconnected-(U1B-VBAT-Pad1)") (class "Default")
      (node (ref "U1") (pin "1") (pinfunction "VBAT_1") (pintype "power_in"))
    )
    (net (code "95") (name "unconnected-(U3-ANA_TEST0-Pad3)") (class "Default")
      (node (ref "U3") (pin "3") (pinfunction "ANA_TEST0_3") (pintype "passive"))
    )
    (net (code "96") (name "unconnected-(U3-EXT_LPCLK-Pad1)") (class "Default")
      (node (ref "U3") (pin "1") (pinfunction "EXT_LPCLK_1") (pintype "passive"))
    )
    (net (code "97") (name "unconnected-(U3-GPIO2-Pad2)") (class "Default")
      (node (ref "U3") (pin "2") (pinfunction "GPIO2_2") (pintype "passive"))
    )
  )
)
